# mimic4688.net
KiCad netlist of a schematic drawn in EAGLE
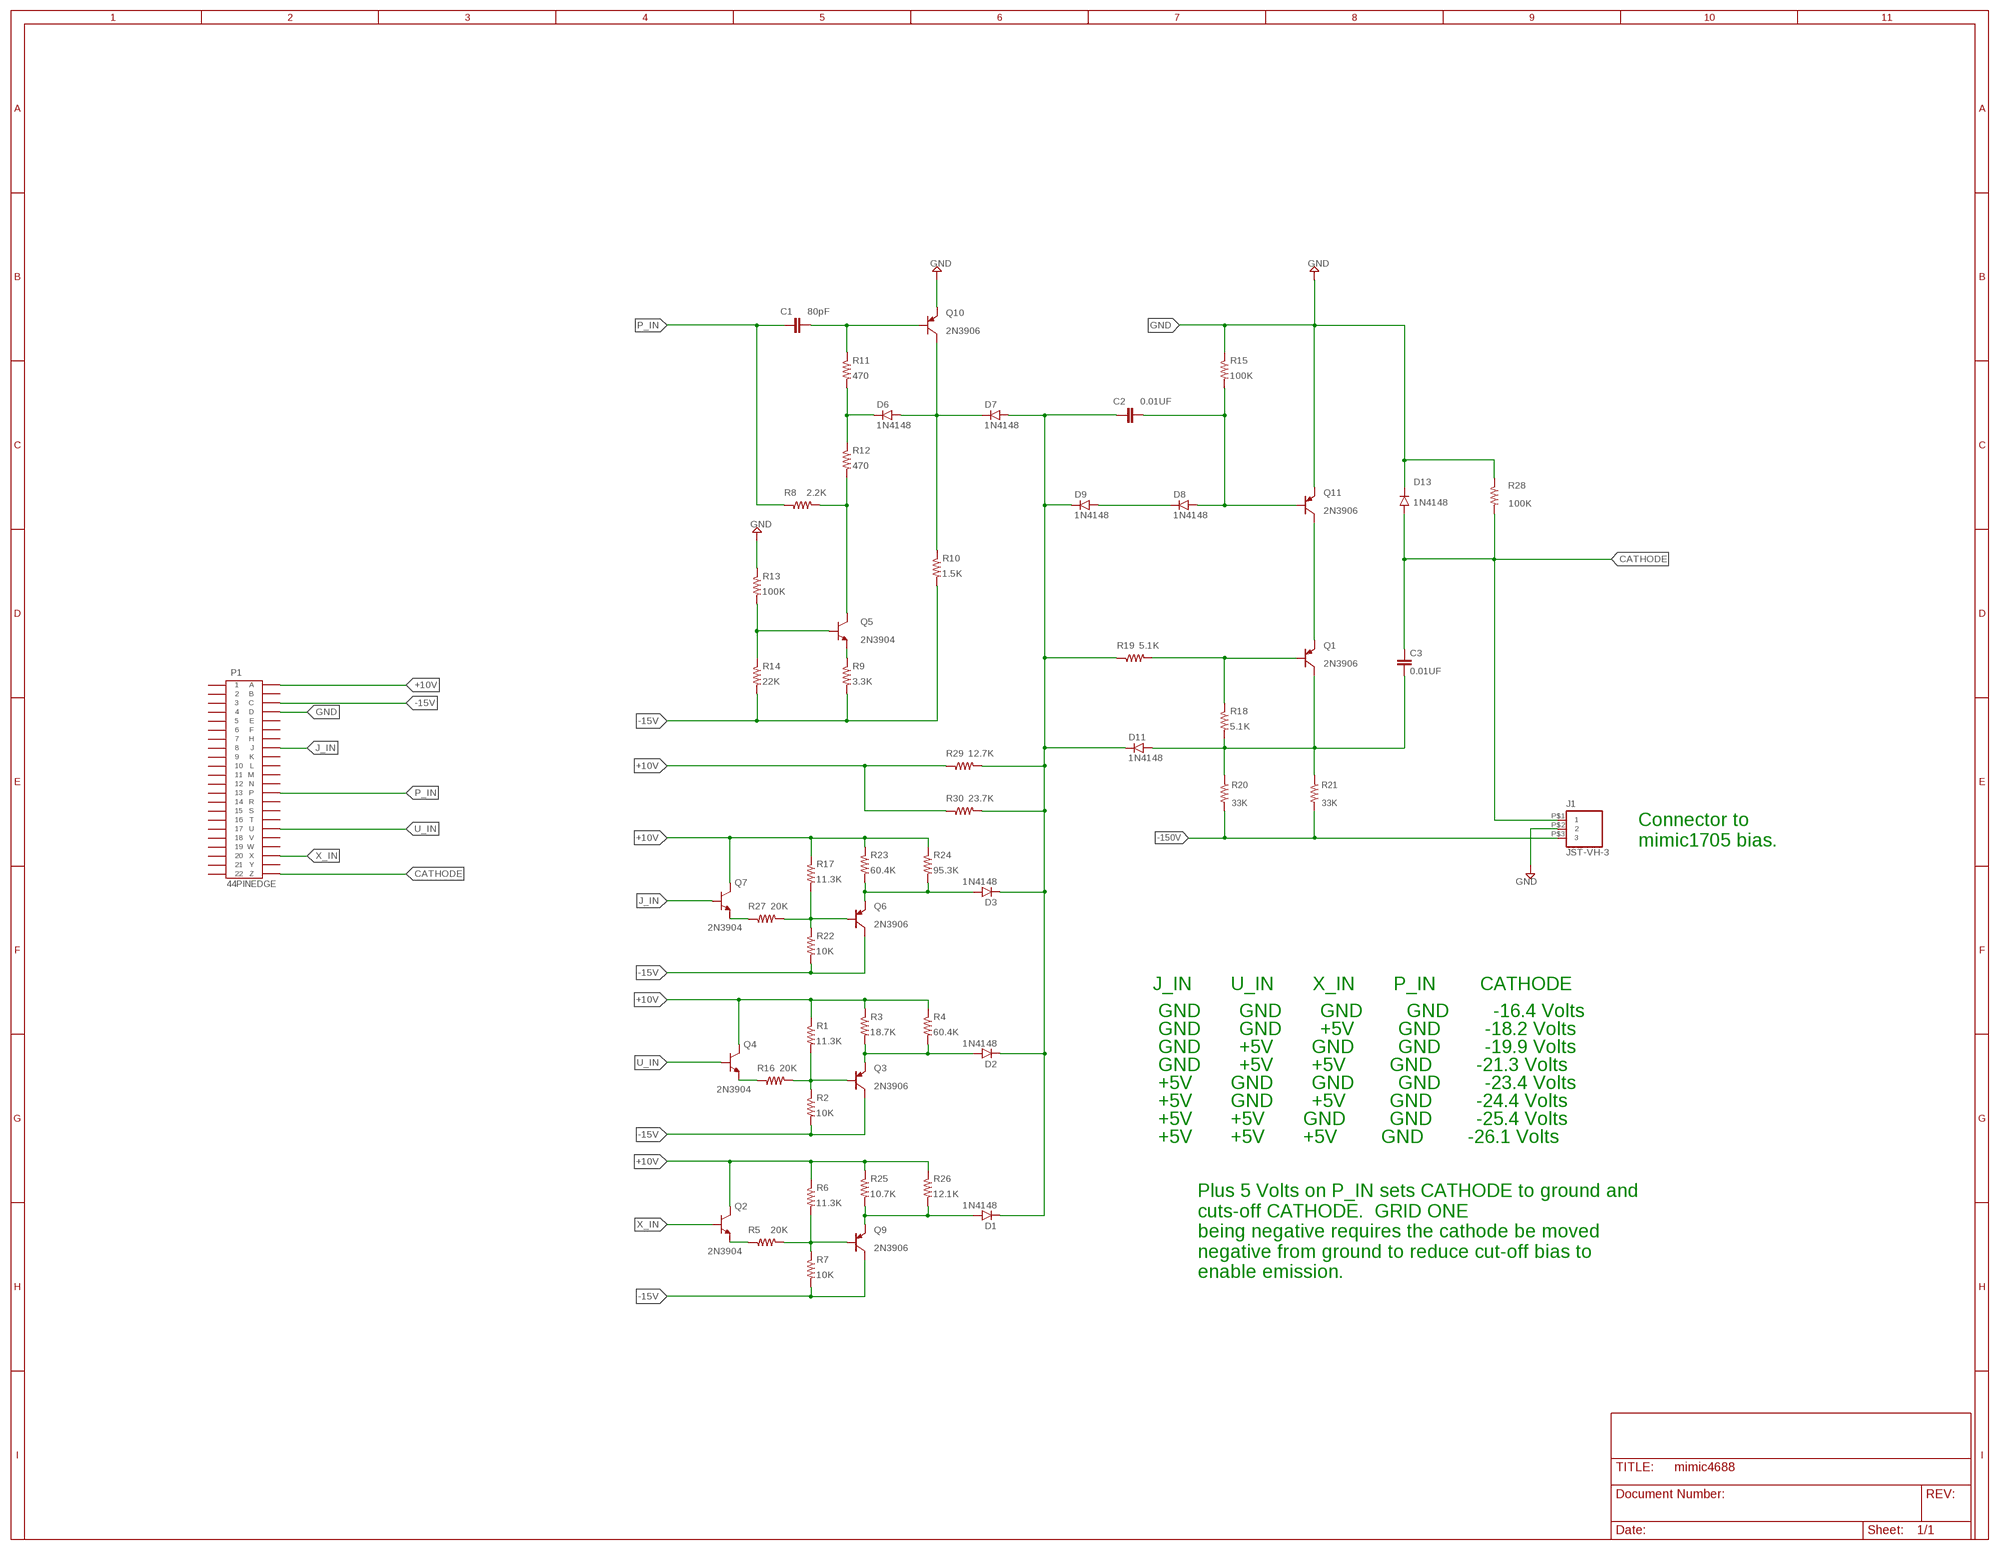
[diagram p0: schematic, sheet 1]

(export (version "E")
  (design (tool "Eeschema 10.0.6"))
  (components
    (comp (ref "C1")
      (value "80pF")
      (footprint "eagle-import:5MM_TH")
      (libsource (lib "eagle-import") (part "CAP_5MM"))
    )
    (comp (ref "C2")
      (value "0.01UF")
      (footprint "eagle-import:5MM_TH")
      (libsource (lib "eagle-import") (part "CAP_5MM"))
    )
    (comp (ref "C3")
      (value "0.01UF")
      (footprint "eagle-import:5MM_TH")
      (libsource (lib "eagle-import") (part "CAP_5MM"))
    )
    (comp (ref "D1")
      (value "1N4148")
      (footprint "eagle-import:DO35-7")
      (libsource (lib "eagle-import") (part "1N4148"))
    )
    (comp (ref "D2")
      (value "1N4148")
      (footprint "eagle-import:DO35-7")
      (libsource (lib "eagle-import") (part "1N4148"))
    )
    (comp (ref "D3")
      (value "1N4148")
      (footprint "eagle-import:DO35-7")
      (libsource (lib "eagle-import") (part "1N4148"))
    )
    (comp (ref "D6")
      (value "1N4148")
      (footprint "eagle-import:DO35-7")
      (libsource (lib "eagle-import") (part "1N4148"))
    )
    (comp (ref "D7")
      (value "1N4148")
      (footprint "eagle-import:DO35-7")
      (libsource (lib "eagle-import") (part "1N4148"))
    )
    (comp (ref "D8")
      (value "1N4148")
      (footprint "eagle-import:DO35-7")
      (libsource (lib "eagle-import") (part "1N4148"))
    )
    (comp (ref "D9")
      (value "1N4148")
      (footprint "eagle-import:DO35-7")
      (libsource (lib "eagle-import") (part "1N4148"))
    )
    (comp (ref "D11")
      (value "1N4148")
      (footprint "eagle-import:DO35-7")
      (libsource (lib "eagle-import") (part "1N4148"))
    )
    (comp (ref "D13")
      (value "1N4148")
      (footprint "eagle-import:DO35-7")
      (libsource (lib "eagle-import") (part "1N4148"))
    )
    (comp (ref "J1")
      (value "JST-VH-3")
      (footprint "eagle-import:VHR-3N")
      (libsource (lib "eagle-import") (part "JST-VH-3"))
    )
    (comp (ref "P1")
      (value "44PINEDGE")
      (footprint "eagle-import:44PINEDGE")
      (libsource (lib "eagle-import") (part "44PINEDGE"))
    )
    (comp (ref "Q1")
      (value "2N3906")
      (footprint "eagle-import:TO92")
      (libsource (lib "eagle-import") (part "2N3906"))
    )
    (comp (ref "Q2")
      (value "2N3904")
      (footprint "eagle-import:TO92")
      (libsource (lib "eagle-import") (part "2N3904"))
    )
    (comp (ref "Q3")
      (value "2N3906")
      (footprint "eagle-import:TO92")
      (libsource (lib "eagle-import") (part "2N3906"))
    )
    (comp (ref "Q4")
      (value "2N3904")
      (footprint "eagle-import:TO92")
      (libsource (lib "eagle-import") (part "2N3904"))
    )
    (comp (ref "Q5")
      (value "2N3904")
      (footprint "eagle-import:TO92")
      (libsource (lib "eagle-import") (part "2N3904"))
    )
    (comp (ref "Q6")
      (value "2N3906")
      (footprint "eagle-import:TO92")
      (libsource (lib "eagle-import") (part "2N3906"))
    )
    (comp (ref "Q7")
      (value "2N3904")
      (footprint "eagle-import:TO92")
      (libsource (lib "eagle-import") (part "2N3904"))
    )
    (comp (ref "Q9")
      (value "2N3906")
      (footprint "eagle-import:TO92")
      (libsource (lib "eagle-import") (part "2N3906"))
    )
    (comp (ref "Q10")
      (value "2N3906")
      (footprint "eagle-import:TO92")
      (libsource (lib "eagle-import") (part "2N3906"))
    )
    (comp (ref "Q11")
      (value "2N3906")
      (footprint "eagle-import:TO92")
      (libsource (lib "eagle-import") (part "2N3906"))
    )
    (comp (ref "R1")
      (value "11.3K")
      (footprint "eagle-import:0207_10")
      (libsource (lib "eagle-import") (part "R-1/4WATT"))
    )
    (comp (ref "R2")
      (value "10K")
      (footprint "eagle-import:0207_10")
      (libsource (lib "eagle-import") (part "R-1/4WATT"))
    )
    (comp (ref "R3")
      (value "18.7K")
      (footprint "eagle-import:0207_10")
      (libsource (lib "eagle-import") (part "R-1/4WATT"))
    )
    (comp (ref "R4")
      (value "60.4K")
      (footprint "eagle-import:0207_10")
      (libsource (lib "eagle-import") (part "R-1/4WATT"))
    )
    (comp (ref "R5")
      (value "20K")
      (footprint "eagle-import:0207_10")
      (libsource (lib "eagle-import") (part "R-1/4WATT"))
    )
    (comp (ref "R6")
      (value "11.3K")
      (footprint "eagle-import:0207_10")
      (libsource (lib "eagle-import") (part "R-1/4WATT"))
    )
    (comp (ref "R7")
      (value "10K")
      (footprint "eagle-import:0207_10")
      (libsource (lib "eagle-import") (part "R-1/4WATT"))
    )
    (comp (ref "R8")
      (value "2.2K")
      (footprint "eagle-import:0207_10")
      (libsource (lib "eagle-import") (part "R-1/4WATT"))
    )
    (comp (ref "R9")
      (value "3.3K")
      (footprint "eagle-import:0207_10")
      (libsource (lib "eagle-import") (part "R-1/4WATT"))
    )
    (comp (ref "R10")
      (value "1.5K")
      (footprint "eagle-import:0207_10")
      (libsource (lib "eagle-import") (part "R-1/4WATT"))
    )
    (comp (ref "R11")
      (value "470")
      (footprint "eagle-import:0207_10")
      (libsource (lib "eagle-import") (part "R-1/4WATT"))
    )
    (comp (ref "R12")
      (value "470")
      (footprint "eagle-import:0207_10")
      (libsource (lib "eagle-import") (part "R-1/4WATT"))
    )
    (comp (ref "R13")
      (value "100K")
      (footprint "eagle-import:0207_10")
      (libsource (lib "eagle-import") (part "R-1/4WATT"))
    )
    (comp (ref "R14")
      (value "22K")
      (footprint "eagle-import:0207_10")
      (libsource (lib "eagle-import") (part "R-1/4WATT"))
    )
    (comp (ref "R15")
      (value "100K")
      (footprint "eagle-import:0207_10")
      (libsource (lib "eagle-import") (part "R-1/4WATT"))
    )
    (comp (ref "R16")
      (value "20K")
      (footprint "eagle-import:0207_10")
      (libsource (lib "eagle-import") (part "R-1/4WATT"))
    )
    (comp (ref "R17")
      (value "11.3K")
      (footprint "eagle-import:0207_10")
      (libsource (lib "eagle-import") (part "R-1/4WATT"))
    )
    (comp (ref "R18")
      (value "5.1K")
      (footprint "eagle-import:0207_10")
      (libsource (lib "eagle-import") (part "R-1/4WATT"))
    )
    (comp (ref "R19")
      (value "5.1K")
      (footprint "eagle-import:0207_10")
      (libsource (lib "eagle-import") (part "R-1/4WATT"))
    )
    (comp (ref "R20")
      (value "33K")
      (footprint "eagle-import:RR02")
      (libsource (lib "eagle-import") (part "RES33K2W"))
    )
    (comp (ref "R21")
      (value "33K")
      (footprint "eagle-import:RR02")
      (libsource (lib "eagle-import") (part "RES33K2W"))
    )
    (comp (ref "R22")
      (value "10K")
      (footprint "eagle-import:0207_10")
      (libsource (lib "eagle-import") (part "R-1/4WATT"))
    )
    (comp (ref "R23")
      (value "60.4K")
      (footprint "eagle-import:0207_10")
      (libsource (lib "eagle-import") (part "R-1/4WATT"))
    )
    (comp (ref "R24")
      (value "95.3K")
      (footprint "eagle-import:0207_10")
      (libsource (lib "eagle-import") (part "R-1/4WATT"))
    )
    (comp (ref "R25")
      (value "10.7K")
      (footprint "eagle-import:0207_10")
      (libsource (lib "eagle-import") (part "R-1/4WATT"))
    )
    (comp (ref "R26")
      (value "12.1K")
      (footprint "eagle-import:0207_10")
      (libsource (lib "eagle-import") (part "R-1/4WATT"))
    )
    (comp (ref "R27")
      (value "20K")
      (footprint "eagle-import:0207_10")
      (libsource (lib "eagle-import") (part "R-1/4WATT"))
    )
    (comp (ref "R28")
      (value "100K")
      (footprint "eagle-import:0207_10")
      (libsource (lib "eagle-import") (part "R-1/4WATT"))
    )
    (comp (ref "R29")
      (value "12.7K")
      (footprint "eagle-import:0207_10")
      (libsource (lib "eagle-import") (part "R-1/4WATT"))
    )
    (comp (ref "R30")
      (value "23.7K")
      (footprint "eagle-import:0207_10")
      (libsource (lib "eagle-import") (part "R-1/4WATT"))
    )
  )
  (nets
    (net (code "1") (name "+10V") (class "Default")
      (node (ref "P1") (pin "A") (pinfunction "A_A") (pintype "passive"))
      (node (ref "Q2") (pin "3") (pinfunction "C_3") (pintype "passive"))
      (node (ref "Q4") (pin "3") (pinfunction "C_3") (pintype "passive"))
      (node (ref "Q7") (pin "3") (pinfunction "C_3") (pintype "passive"))
      (node (ref "R1") (pin "1") (pinfunction "P$1_1") (pintype "passive"))
      (node (ref "R17") (pin "1") (pinfunction "P$1_1") (pintype "passive"))
      (node (ref "R23") (pin "1") (pinfunction "P$1_1") (pintype "passive"))
      (node (ref "R24") (pin "1") (pinfunction "P$1_1") (pintype "passive"))
      (node (ref "R25") (pin "1") (pinfunction "P$1_1") (pintype "passive"))
      (node (ref "R26") (pin "1") (pinfunction "P$1_1") (pintype "passive"))
      (node (ref "R29") (pin "1") (pinfunction "P$1_1") (pintype "passive"))
      (node (ref "R3") (pin "1") (pinfunction "P$1_1") (pintype "passive"))
      (node (ref "R30") (pin "1") (pinfunction "P$1_1") (pintype "passive"))
      (node (ref "R4") (pin "1") (pinfunction "P$1_1") (pintype "passive"))
      (node (ref "R6") (pin "1") (pinfunction "P$1_1") (pintype "passive"))
    )
    (net (code "2") (name "-15V") (class "Default")
      (node (ref "P1") (pin "C") (pinfunction "C_C") (pintype "passive"))
      (node (ref "Q3") (pin "1") (pinfunction "C_1") (pintype "passive"))
      (node (ref "Q6") (pin "1") (pinfunction "C_1") (pintype "passive"))
      (node (ref "Q9") (pin "1") (pinfunction "C_1") (pintype "passive"))
      (node (ref "R10") (pin "2") (pinfunction "P$2_2") (pintype "passive"))
      (node (ref "R14") (pin "2") (pinfunction "P$2_2") (pintype "passive"))
      (node (ref "R2") (pin "2") (pinfunction "P$2_2") (pintype "passive"))
      (node (ref "R22") (pin "2") (pinfunction "P$2_2") (pintype "passive"))
      (node (ref "R7") (pin "2") (pinfunction "P$2_2") (pintype "passive"))
      (node (ref "R9") (pin "2") (pinfunction "P$2_2") (pintype "passive"))
    )
    (net (code "3") (name "-150V") (class "Default")
      (node (ref "J1") (pin "P$3") (pinfunction "3_P$3") (pintype "bidirectional"))
      (node (ref "R20") (pin "2") (pinfunction "P$2_2") (pintype "passive"))
      (node (ref "R21") (pin "2") (pinfunction "P$2_2") (pintype "passive"))
    )
    (net (code "4") (name "CATHODE") (class "Default")
      (node (ref "C3") (pin "1") (pinfunction "1_1") (pintype "passive"))
      (node (ref "D13") (pin "A") (pinfunction "A_A") (pintype "passive"))
      (node (ref "J1") (pin "P$1") (pinfunction "1_P$1") (pintype "bidirectional"))
      (node (ref "P1") (pin "Z") (pinfunction "Z_Z") (pintype "passive"))
      (node (ref "R28") (pin "2") (pinfunction "P$2_2") (pintype "passive"))
    )
    (net (code "5") (name "GND") (class "Default")
      (node (ref "D13") (pin "C") (pinfunction "C_C") (pintype "passive"))
      (node (ref "J1") (pin "P$2") (pinfunction "2_P$2") (pintype "bidirectional"))
      (node (ref "P1") (pin "D") (pinfunction "D_D") (pintype "passive"))
      (node (ref "Q10") (pin "3") (pinfunction "E_3") (pintype "passive"))
      (node (ref "Q11") (pin "3") (pinfunction "E_3") (pintype "passive"))
      (node (ref "R13") (pin "1") (pinfunction "P$1_1") (pintype "passive"))
      (node (ref "R15") (pin "1") (pinfunction "P$1_1") (pintype "passive"))
      (node (ref "R28") (pin "1") (pinfunction "P$1_1") (pintype "passive"))
    )
    (net (code "6") (name "J_IN") (class "Default")
      (node (ref "P1") (pin "J") (pinfunction "J_J") (pintype "passive"))
      (node (ref "Q7") (pin "2") (pinfunction "B_2") (pintype "passive"))
    )
    (net (code "7") (name "Net-(D8-PadC)") (class "Default")
      (node (ref "D8") (pin "C") (pinfunction "C_C") (pintype "passive"))
      (node (ref "D9") (pin "A") (pinfunction "A_A") (pintype "passive"))
    )
    (net (code "8") (name "Net-(Q1-B)") (class "Default")
      (node (ref "Q1") (pin "2") (pinfunction "B_2") (pintype "passive"))
      (node (ref "R18") (pin "1") (pinfunction "P$1_1") (pintype "passive"))
      (node (ref "R19") (pin "2") (pinfunction "P$2_2") (pintype "passive"))
    )
    (net (code "9") (name "Net-(Q1-C)") (class "Default")
      (node (ref "C3") (pin "2") (pinfunction "2_2") (pintype "passive"))
      (node (ref "D11") (pin "A") (pinfunction "A_A") (pintype "passive"))
      (node (ref "Q1") (pin "1") (pinfunction "C_1") (pintype "passive"))
      (node (ref "R18") (pin "2") (pinfunction "P$2_2") (pintype "passive"))
      (node (ref "R20") (pin "1") (pinfunction "P$1_1") (pintype "passive"))
      (node (ref "R21") (pin "1") (pinfunction "P$1_1") (pintype "passive"))
    )
    (net (code "10") (name "Net-(Q1-E)") (class "Default")
      (node (ref "Q1") (pin "3") (pinfunction "E_3") (pintype "passive"))
      (node (ref "Q11") (pin "1") (pinfunction "C_1") (pintype "passive"))
    )
    (net (code "11") (name "Net-(Q2-E)") (class "Default")
      (node (ref "Q2") (pin "1") (pinfunction "E_1") (pintype "passive"))
      (node (ref "R5") (pin "1") (pinfunction "P$1_1") (pintype "passive"))
    )
    (net (code "12") (name "Net-(Q3-B)") (class "Default")
      (node (ref "Q3") (pin "2") (pinfunction "B_2") (pintype "passive"))
      (node (ref "R1") (pin "2") (pinfunction "P$2_2") (pintype "passive"))
      (node (ref "R16") (pin "2") (pinfunction "P$2_2") (pintype "passive"))
      (node (ref "R2") (pin "1") (pinfunction "P$1_1") (pintype "passive"))
    )
    (net (code "13") (name "Net-(Q3-E)") (class "Default")
      (node (ref "D2") (pin "A") (pinfunction "A_A") (pintype "passive"))
      (node (ref "Q3") (pin "3") (pinfunction "E_3") (pintype "passive"))
      (node (ref "R3") (pin "2") (pinfunction "P$2_2") (pintype "passive"))
      (node (ref "R4") (pin "2") (pinfunction "P$2_2") (pintype "passive"))
    )
    (net (code "14") (name "Net-(Q4-E)") (class "Default")
      (node (ref "Q4") (pin "1") (pinfunction "E_1") (pintype "passive"))
      (node (ref "R16") (pin "1") (pinfunction "P$1_1") (pintype "passive"))
    )
    (net (code "15") (name "Net-(Q5-B)") (class "Default")
      (node (ref "Q5") (pin "2") (pinfunction "B_2") (pintype "passive"))
      (node (ref "R13") (pin "2") (pinfunction "P$2_2") (pintype "passive"))
      (node (ref "R14") (pin "1") (pinfunction "P$1_1") (pintype "passive"))
    )
    (net (code "16") (name "Net-(Q5-C)") (class "Default")
      (node (ref "Q5") (pin "3") (pinfunction "C_3") (pintype "passive"))
      (node (ref "R12") (pin "2") (pinfunction "P$2_2") (pintype "passive"))
      (node (ref "R8") (pin "2") (pinfunction "P$2_2") (pintype "passive"))
    )
    (net (code "17") (name "Net-(Q5-E)") (class "Default")
      (node (ref "Q5") (pin "1") (pinfunction "E_1") (pintype "passive"))
      (node (ref "R9") (pin "1") (pinfunction "P$1_1") (pintype "passive"))
    )
    (net (code "18") (name "Net-(Q6-B)") (class "Default")
      (node (ref "Q6") (pin "2") (pinfunction "B_2") (pintype "passive"))
      (node (ref "R17") (pin "2") (pinfunction "P$2_2") (pintype "passive"))
      (node (ref "R22") (pin "1") (pinfunction "P$1_1") (pintype "passive"))
      (node (ref "R27") (pin "2") (pinfunction "P$2_2") (pintype "passive"))
    )
    (net (code "19") (name "Net-(Q6-E)") (class "Default")
      (node (ref "D3") (pin "A") (pinfunction "A_A") (pintype "passive"))
      (node (ref "Q6") (pin "3") (pinfunction "E_3") (pintype "passive"))
      (node (ref "R23") (pin "2") (pinfunction "P$2_2") (pintype "passive"))
      (node (ref "R24") (pin "2") (pinfunction "P$2_2") (pintype "passive"))
    )
    (net (code "20") (name "Net-(Q7-E)") (class "Default")
      (node (ref "Q7") (pin "1") (pinfunction "E_1") (pintype "passive"))
      (node (ref "R27") (pin "1") (pinfunction "P$1_1") (pintype "passive"))
    )
    (net (code "21") (name "Net-(Q9-B)") (class "Default")
      (node (ref "Q9") (pin "2") (pinfunction "B_2") (pintype "passive"))
      (node (ref "R5") (pin "2") (pinfunction "P$2_2") (pintype "passive"))
      (node (ref "R6") (pin "2") (pinfunction "P$2_2") (pintype "passive"))
      (node (ref "R7") (pin "1") (pinfunction "P$1_1") (pintype "passive"))
    )
    (net (code "22") (name "Net-(Q9-E)") (class "Default")
      (node (ref "D1") (pin "A") (pinfunction "A_A") (pintype "passive"))
      (node (ref "Q9") (pin "3") (pinfunction "E_3") (pintype "passive"))
      (node (ref "R25") (pin "2") (pinfunction "P$2_2") (pintype "passive"))
      (node (ref "R26") (pin "2") (pinfunction "P$2_2") (pintype "passive"))
    )
    (net (code "23") (name "Net-(Q10-B)") (class "Default")
      (node (ref "C1") (pin "2") (pinfunction "2_2") (pintype "passive"))
      (node (ref "Q10") (pin "2") (pinfunction "B_2") (pintype "passive"))
      (node (ref "R11") (pin "1") (pinfunction "P$1_1") (pintype "passive"))
    )
    (net (code "24") (name "Net-(Q10-C)") (class "Default")
      (node (ref "D6") (pin "A") (pinfunction "A_A") (pintype "passive"))
      (node (ref "D7") (pin "C") (pinfunction "C_C") (pintype "passive"))
      (node (ref "Q10") (pin "1") (pinfunction "C_1") (pintype "passive"))
      (node (ref "R10") (pin "1") (pinfunction "P$1_1") (pintype "passive"))
    )
    (net (code "25") (name "Net-(Q11-B)") (class "Default")
      (node (ref "C2") (pin "2") (pinfunction "2_2") (pintype "passive"))
      (node (ref "D8") (pin "A") (pinfunction "A_A") (pintype "passive"))
      (node (ref "Q11") (pin "2") (pinfunction "B_2") (pintype "passive"))
      (node (ref "R15") (pin "2") (pinfunction "P$2_2") (pintype "passive"))
    )
    (net (code "26") (name "Net-(R11-P$2)") (class "Default")
      (node (ref "D6") (pin "C") (pinfunction "C_C") (pintype "passive"))
      (node (ref "R11") (pin "2") (pinfunction "P$2_2") (pintype "passive"))
      (node (ref "R12") (pin "1") (pinfunction "P$1_1") (pintype "passive"))
    )
    (net (code "27") (name "Net-(R19-P$1)") (class "Default")
      (node (ref "C2") (pin "1") (pinfunction "1_1") (pintype "passive"))
      (node (ref "D1") (pin "C") (pinfunction "C_C") (pintype "passive"))
      (node (ref "D11") (pin "C") (pinfunction "C_C") (pintype "passive"))
      (node (ref "D2") (pin "C") (pinfunction "C_C") (pintype "passive"))
      (node (ref "D3") (pin "C") (pinfunction "C_C") (pintype "passive"))
      (node (ref "D7") (pin "A") (pinfunction "A_A") (pintype "passive"))
      (node (ref "D9") (pin "C") (pinfunction "C_C") (pintype "passive"))
      (node (ref "R19") (pin "1") (pinfunction "P$1_1") (pintype "passive"))
      (node (ref "R29") (pin "2") (pinfunction "P$2_2") (pintype "passive"))
      (node (ref "R30") (pin "2") (pinfunction "P$2_2") (pintype "passive"))
    )
    (net (code "28") (name "P_IN") (class "Default")
      (node (ref "C1") (pin "1") (pinfunction "1_1") (pintype "passive"))
      (node (ref "P1") (pin "P") (pinfunction "P_P") (pintype "passive"))
      (node (ref "R8") (pin "1") (pinfunction "P$1_1") (pintype "passive"))
    )
    (net (code "29") (name "U_IN") (class "Default")
      (node (ref "P1") (pin "U") (pinfunction "U_U") (pintype "passive"))
      (node (ref "Q4") (pin "2") (pinfunction "B_2") (pintype "passive"))
    )
    (net (code "30") (name "X_IN") (class "Default")
      (node (ref "P1") (pin "X") (pinfunction "X_X") (pintype "passive"))
      (node (ref "Q2") (pin "2") (pinfunction "B_2") (pintype "passive"))
    )
    (net (code "31") (name "unconnected-(P1-Pad1)") (class "Default")
      (node (ref "P1") (pin "1") (pinfunction "1_1") (pintype "passive"))
    )
    (net (code "32") (name "unconnected-(P1-Pad2)") (class "Default")
      (node (ref "P1") (pin "2") (pinfunction "2_2") (pintype "passive"))
    )
    (net (code "33") (name "unconnected-(P1-Pad3)") (class "Default")
      (node (ref "P1") (pin "3") (pinfunction "3_3") (pintype "passive"))
    )
    (net (code "34") (name "unconnected-(P1-Pad4)") (class "Default")
      (node (ref "P1") (pin "4") (pinfunction "4_4") (pintype "passive"))
    )
    (net (code "35") (name "unconnected-(P1-Pad5)") (class "Default")
      (node (ref "P1") (pin "5") (pinfunction "5_5") (pintype "passive"))
    )
    (net (code "36") (name "unconnected-(P1-Pad6)") (class "Default")
      (node (ref "P1") (pin "6") (pinfunction "6_6") (pintype "passive"))
    )
    (net (code "37") (name "unconnected-(P1-Pad7)") (class "Default")
      (node (ref "P1") (pin "7") (pinfunction "7_7") (pintype "passive"))
    )
    (net (code "38") (name "unconnected-(P1-Pad8)") (class "Default")
      (node (ref "P1") (pin "8") (pinfunction "8_8") (pintype "passive"))
    )
    (net (code "39") (name "unconnected-(P1-Pad9)") (class "Default")
      (node (ref "P1") (pin "9") (pinfunction "9_9") (pintype "passive"))
    )
    (net (code "40") (name "unconnected-(P1-Pad10)") (class "Default")
      (node (ref "P1") (pin "10") (pinfunction "10_10") (pintype "passive"))
    )
    (net (code "41") (name "unconnected-(P1-Pad11)") (class "Default")
      (node (ref "P1") (pin "11") (pinfunction "11_11") (pintype "passive"))
    )
    (net (code "42") (name "unconnected-(P1-Pad12)") (class "Default")
      (node (ref "P1") (pin "12") (pinfunction "12_12") (pintype "passive"))
    )
    (net (code "43") (name "unconnected-(P1-Pad13)") (class "Default")
      (node (ref "P1") (pin "13") (pinfunction "13_13") (pintype "passive"))
    )
    (net (code "44") (name "unconnected-(P1-Pad14)") (class "Default")
      (node (ref "P1") (pin "14") (pinfunction "14_14") (pintype "passive"))
    )
    (net (code "45") (name "unconnected-(P1-Pad15)") (class "Default")
      (node (ref "P1") (pin "15") (pinfunction "15_15") (pintype "passive"))
    )
    (net (code "46") (name "unconnected-(P1-Pad16)") (class "Default")
      (node (ref "P1") (pin "16") (pinfunction "16_16") (pintype "passive"))
    )
    (net (code "47") (name "unconnected-(P1-Pad17)") (class "Default")
      (node (ref "P1") (pin "17") (pinfunction "17_17") (pintype "passive"))
    )
    (net (code "48") (name "unconnected-(P1-Pad18)") (class "Default")
      (node (ref "P1") (pin "18") (pinfunction "18_18") (pintype "passive"))
    )
    (net (code "49") (name "unconnected-(P1-Pad19)") (class "Default")
      (node (ref "P1") (pin "19") (pinfunction "19_19") (pintype "passive"))
    )
    (net (code "50") (name "unconnected-(P1-Pad20)") (class "Default")
      (node (ref "P1") (pin "20") (pinfunction "20_20") (pintype "passive"))
    )
    (net (code "51") (name "unconnected-(P1-Pad21)") (class "Default")
      (node (ref "P1") (pin "21") (pinfunction "21_21") (pintype "passive"))
    )
    (net (code "52") (name "unconnected-(P1-Pad22)") (class "Default")
      (node (ref "P1") (pin "22") (pinfunction "22_22") (pintype "passive"))
    )
    (net (code "53") (name "unconnected-(P1-PadB)") (class "Default")
      (node (ref "P1") (pin "B") (pinfunction "B_B") (pintype "passive"))
    )
    (net (code "54") (name "unconnected-(P1-PadE)") (class "Default")
      (node (ref "P1") (pin "E") (pinfunction "E_E") (pintype "passive"))
    )
    (net (code "55") (name "unconnected-(P1-PadF)") (class "Default")
      (node (ref "P1") (pin "F") (pinfunction "F_F") (pintype "passive"))
    )
    (net (code "56") (name "unconnected-(P1-PadH)") (class "Default")
      (node (ref "P1") (pin "H") (pinfunction "H_H") (pintype "passive"))
    )
    (net (code "57") (name "unconnected-(P1-PadK)") (class "Default")
      (node (ref "P1") (pin "K") (pinfunction "K_K") (pintype "passive"))
    )
    (net (code "58") (name "unconnected-(P1-PadL)") (class "Default")
      (node (ref "P1") (pin "L") (pinfunction "L_L") (pintype "passive"))
    )
    (net (code "59") (name "unconnected-(P1-PadM)") (class "Default")
      (node (ref "P1") (pin "M") (pinfunction "M_M") (pintype "passive"))
    )
    (net (code "60") (name "unconnected-(P1-PadN)") (class "Default")
      (node (ref "P1") (pin "N") (pinfunction "N_N") (pintype "passive"))
    )
    (net (code "61") (name "unconnected-(P1-PadR)") (class "Default")
      (node (ref "P1") (pin "R") (pinfunction "R_R") (pintype "passive"))
    )
    (net (code "62") (name "unconnected-(P1-PadS)") (class "Default")
      (node (ref "P1") (pin "S") (pinfunction "S_S") (pintype "passive"))
    )
    (net (code "63") (name "unconnected-(P1-PadT)") (class "Default")
      (node (ref "P1") (pin "T") (pinfunction "T_T") (pintype "passive"))
    )
    (net (code "64") (name "unconnected-(P1-PadV)") (class "Default")
      (node (ref "P1") (pin "V") (pinfunction "V_V") (pintype "passive"))
    )
    (net (code "65") (name "unconnected-(P1-PadW)") (class "Default")
      (node (ref "P1") (pin "W") (pinfunction "W_W") (pintype "passive"))
    )
    (net (code "66") (name "unconnected-(P1-PadY)") (class "Default")
      (node (ref "P1") (pin "Y") (pinfunction "Y_Y") (pintype "passive"))
    )
  )
)
